# eNode_Spark.net
KiCad netlist of a schematic drawn in EAGLE
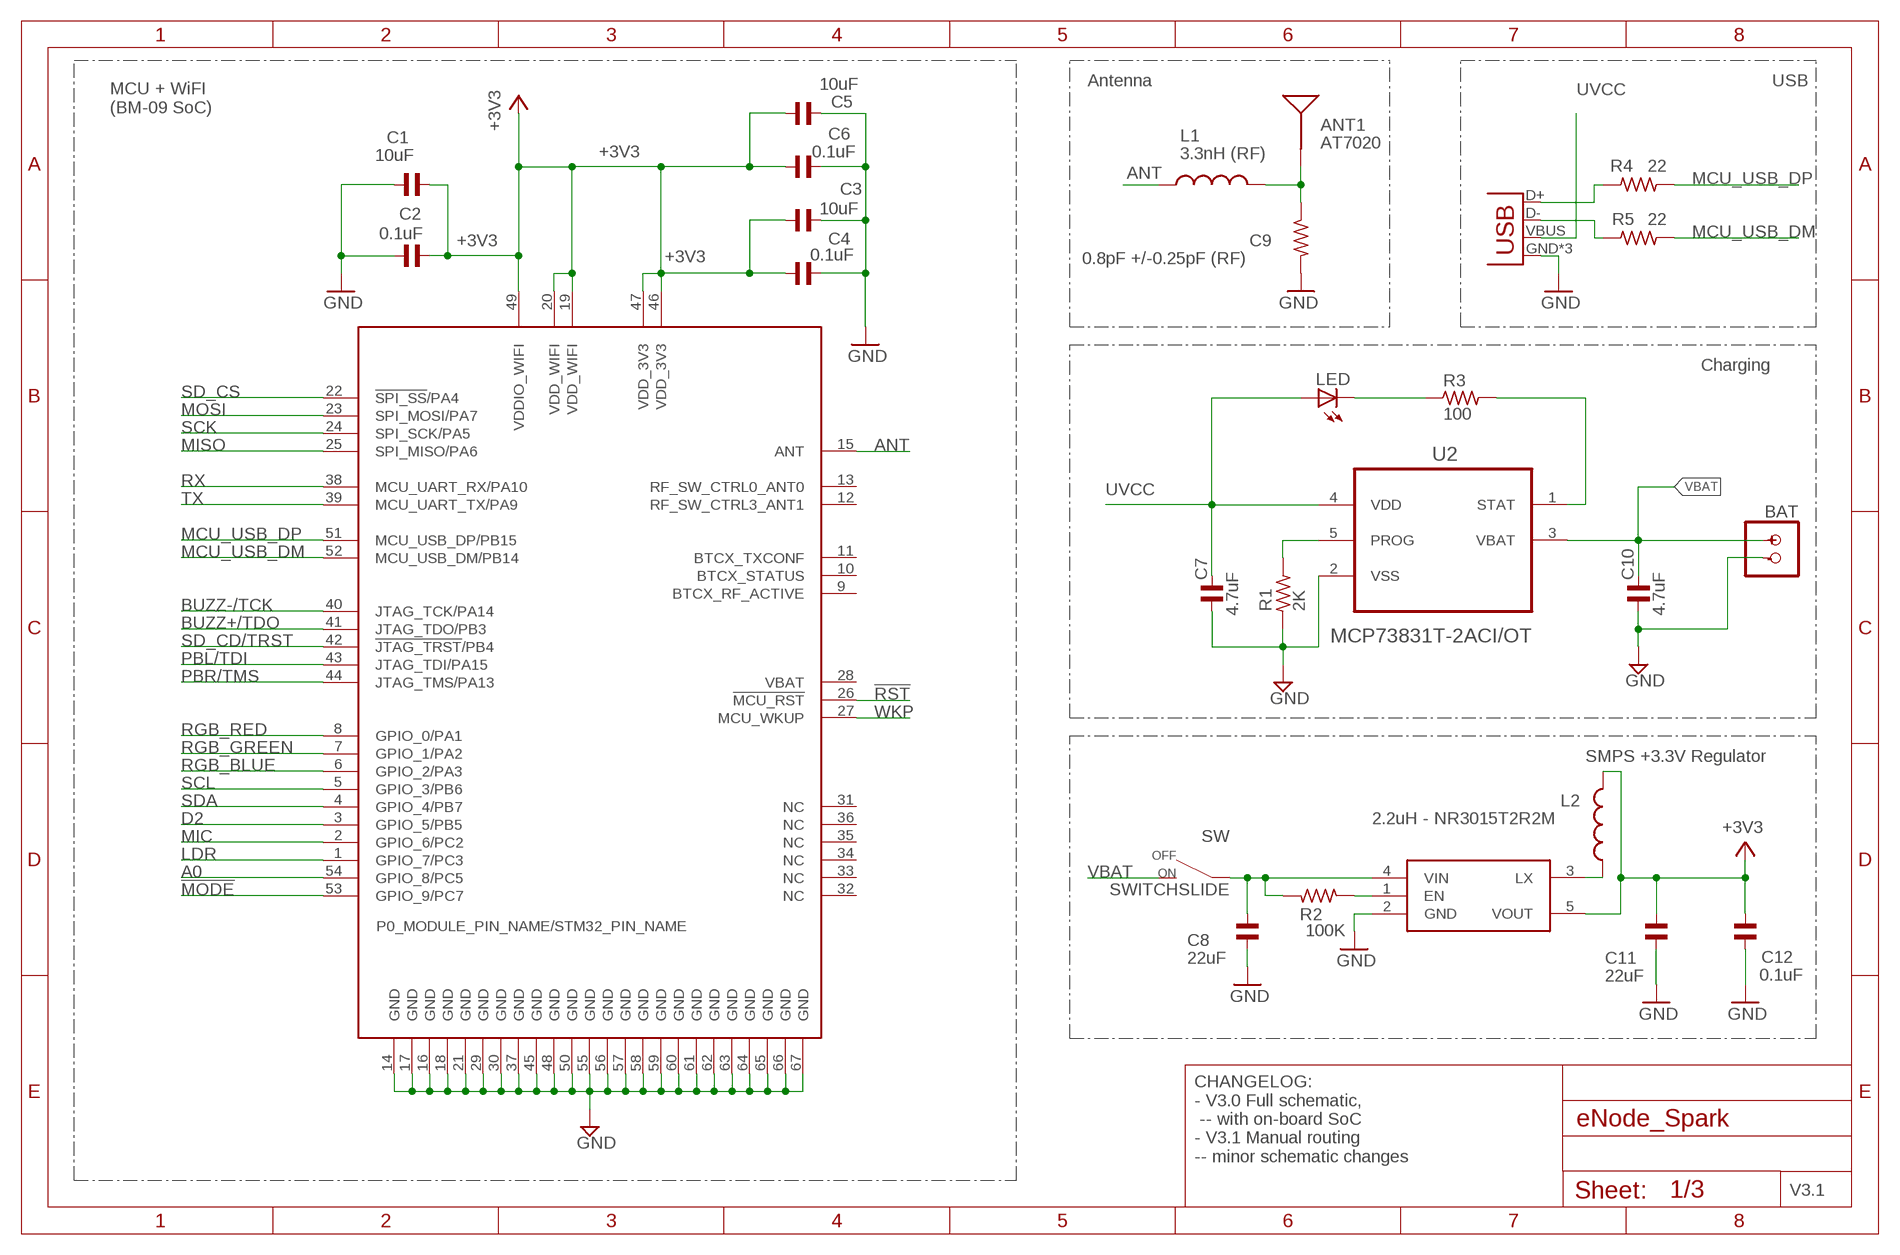
[diagram p0: schematic, sheet 1]
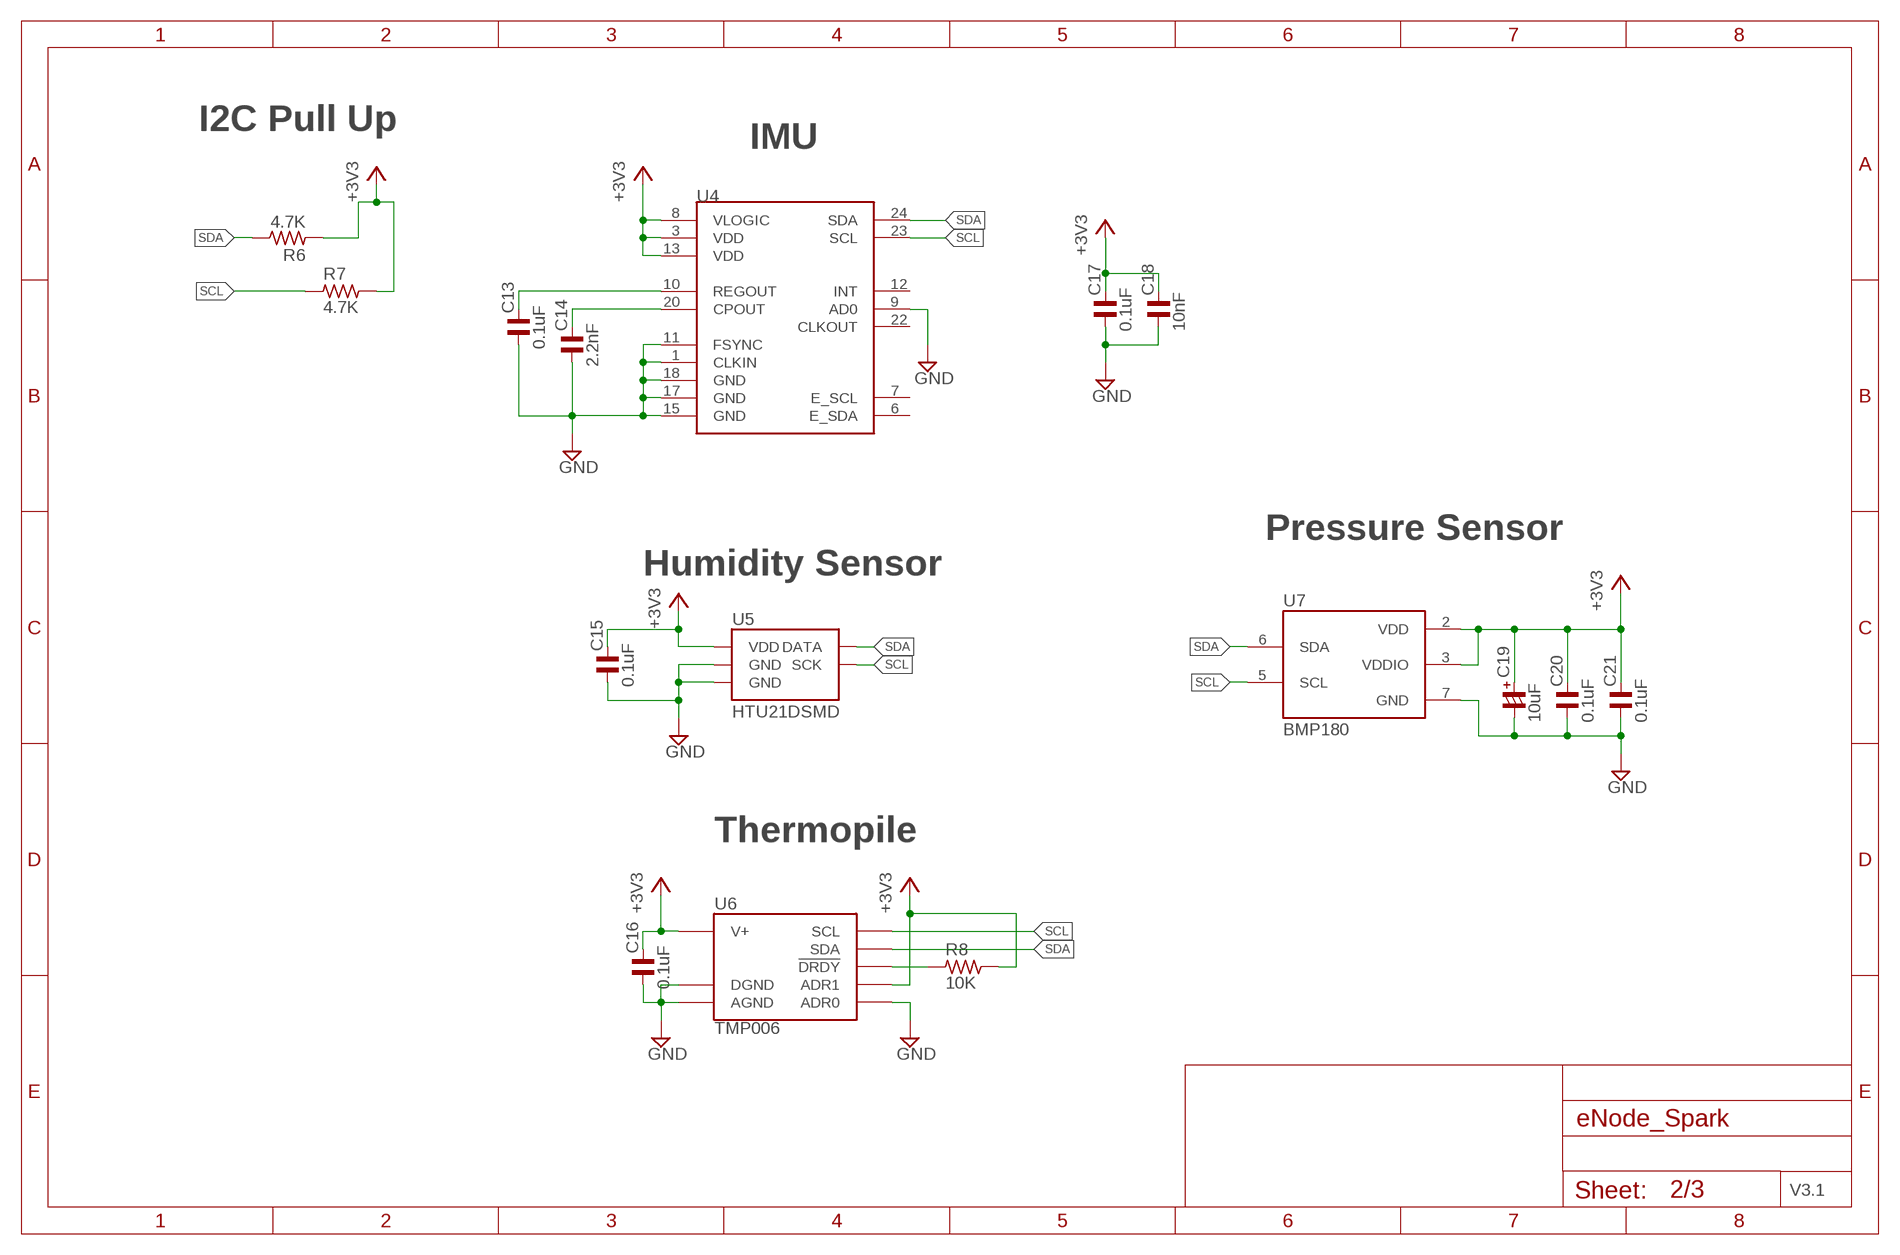
[diagram p1: schematic, sheet 2]
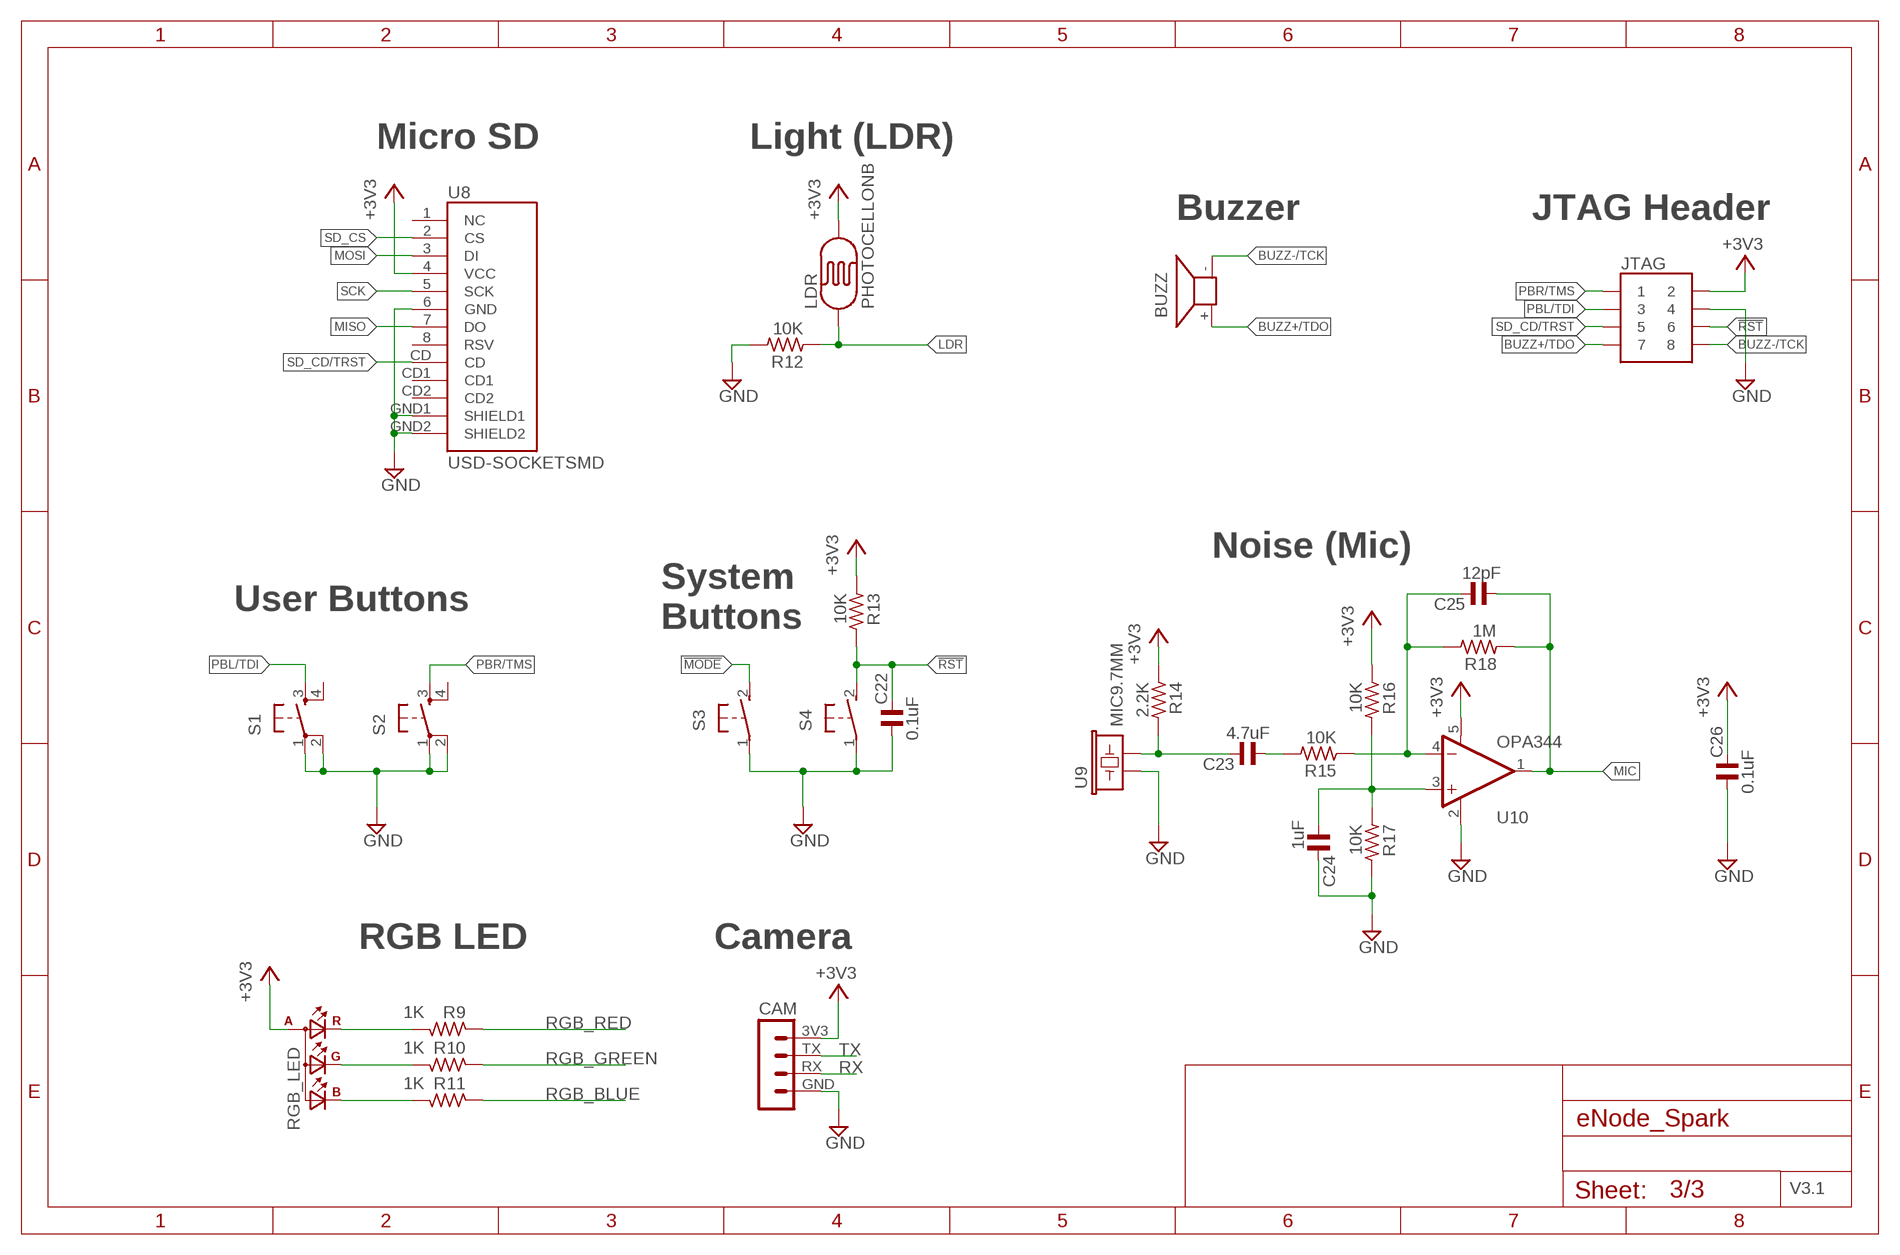
[diagram p2: schematic, sheet 3]

(export (version "E")
  (design (tool "Eeschema 10.0.6"))
  (components
    (comp (ref "ANT1")
      (value "AT7020")
      (footprint "eagle-import:AT7020")
      (libsource (lib "eagle-import") (part "AT7020"))
    )
    (comp (ref "BAT")
      (value "BATTERYSMT")
      (footprint "eagle-import:JST-2-SMD")
      (libsource (lib "eagle-import") (part "BATTERYSMT"))
    )
    (comp (ref "C1")
      (value "10uF")
      (footprint "eagle-import:C0402")
      (libsource (lib "eagle-import") (part "C_0402"))
    )
    (comp (ref "C2")
      (value "0.1uF")
      (footprint "eagle-import:C0402")
      (libsource (lib "eagle-import") (part "C_0402"))
    )
    (comp (ref "C3")
      (value "10uF")
      (footprint "eagle-import:C0402")
      (libsource (lib "eagle-import") (part "C_0402"))
    )
    (comp (ref "C4")
      (value "0.1uF")
      (footprint "eagle-import:C0402")
      (libsource (lib "eagle-import") (part "C_0402"))
    )
    (comp (ref "C5")
      (value "10uF")
      (footprint "eagle-import:C0402")
      (libsource (lib "eagle-import") (part "C_0402"))
    )
    (comp (ref "C6")
      (value "0.1uF")
      (footprint "eagle-import:C0402")
      (libsource (lib "eagle-import") (part "C_0402"))
    )
    (comp (ref "C7")
      (value "4.7uF")
      (footprint "eagle-import:C0402")
      (libsource (lib "eagle-import") (part "C_0402"))
    )
    (comp (ref "C8")
      (value "22uF")
      (footprint "eagle-import:C0603")
      (libsource (lib "eagle-import") (part "C_0603"))
    )
    (comp (ref "C9")
      (value "0.8pF +/-0.25pF (RF)")
      (footprint "eagle-import:R0402_B")
      (libsource (lib "eagle-import") (part "R-US_"))
    )
    (comp (ref "C10")
      (value "4.7uF")
      (footprint "eagle-import:C0402")
      (libsource (lib "eagle-import") (part "C_0402"))
    )
    (comp (ref "C11")
      (value "22uF")
      (footprint "eagle-import:C0603")
      (libsource (lib "eagle-import") (part "C_0603"))
    )
    (comp (ref "C12")
      (value "0.1uF")
      (footprint "eagle-import:C0402")
      (libsource (lib "eagle-import") (part "C_0402"))
    )
    (comp (ref "L1")
      (value "3.3nH (RF)")
      (footprint "eagle-import:L0402_B")
      (libsource (lib "eagle-import") (part "INDUCTOR"))
    )
    (comp (ref "L2")
      (value "2.2uH - NR3015T2R2M")
      (footprint "eagle-import:INDUCTOR-NR3015")
      (libsource (lib "eagle-import") (part "INDUCTORB"))
    )
    (comp (ref "LED")
      (value "LED")
      (footprint "eagle-import:RA_SMD_LED")
      (libsource (lib "eagle-import") (part "LED"))
    )
    (comp (ref "R1")
      (value "2K")
      (footprint "eagle-import:R0603")
      (libsource (lib "eagle-import") (part "R_0603"))
    )
    (comp (ref "R2")
      (value "100K")
      (footprint "eagle-import:R0402")
      (libsource (lib "eagle-import") (part "R_0402"))
    )
    (comp (ref "R3")
      (value "100")
      (footprint "eagle-import:R0603")
      (libsource (lib "eagle-import") (part "R_0603"))
    )
    (comp (ref "R4")
      (value "22")
      (footprint "eagle-import:R0402")
      (libsource (lib "eagle-import") (part "R_0402"))
    )
    (comp (ref "R5")
      (value "22")
      (footprint "eagle-import:R0402")
      (libsource (lib "eagle-import") (part "R_0402"))
    )
    (comp (ref "SW")
      (value "SWITCHSLIDE")
      (footprint "eagle-import:CHANGE_OVER_SLIDE")
      (libsource (lib "eagle-import") (part "SWITCHSLIDE"))
    )
    (comp (ref "U1")
      (value "WM-N-BM-09")
      (footprint "eagle-import:WM-N-BM-09")
      (libsource (lib "eagle-import") (part "WM-N-BM-09"))
    )
    (comp (ref "U2")
      (value "MCP73831T-2ACI/OT")
      (footprint "eagle-import:SOT95P280X145-5N")
      (libsource (lib "eagle-import") (part "MCP73831T-2ACI/OT"))
    )
    (comp (ref "U3")
      (value "R8008-33")
      (footprint "eagle-import:SOT23-5")
      (libsource (lib "eagle-import") (part "R8008-33"))
    )
    (comp (ref "X1")
      (value "USB-MICROB")
      (footprint "eagle-import:USB-MICROB-SLOT-HOLE")
      (libsource (lib "eagle-import") (part "USBUSB-MICROB-SLOT-HOLE"))
    )
    (comp (ref "C13")
      (value "0.1uF")
      (footprint "eagle-import:C0402")
      (libsource (lib "eagle-import") (part "C_0402"))
    )
    (comp (ref "C14")
      (value "2.2nF")
      (footprint "eagle-import:C0402")
      (libsource (lib "eagle-import") (part "C_0402"))
    )
    (comp (ref "C15")
      (value "0.1uF")
      (footprint "eagle-import:C0402")
      (libsource (lib "eagle-import") (part "C_0402"))
    )
    (comp (ref "C16")
      (value "0.1uF")
      (footprint "eagle-import:C0402")
      (libsource (lib "eagle-import") (part "C_0402"))
    )
    (comp (ref "C17")
      (value "0.1uF")
      (footprint "eagle-import:C0402")
      (libsource (lib "eagle-import") (part "C_0402"))
    )
    (comp (ref "C18")
      (value "10nF")
      (footprint "eagle-import:C0402")
      (libsource (lib "eagle-import") (part "C_0402"))
    )
    (comp (ref "C19")
      (value "10uF")
      (footprint "eagle-import:C1206_T")
      (libsource (lib "eagle-import") (part "CP_1206/T"))
    )
    (comp (ref "C20")
      (value "0.1uF")
      (footprint "eagle-import:C0402")
      (libsource (lib "eagle-import") (part "C_0402"))
    )
    (comp (ref "C21")
      (value "0.1uF")
      (footprint "eagle-import:C0402")
      (libsource (lib "eagle-import") (part "C_0402"))
    )
    (comp (ref "R6")
      (value "4.7K")
      (footprint "eagle-import:R0402")
      (libsource (lib "eagle-import") (part "R_0402"))
    )
    (comp (ref "R7")
      (value "4.7K")
      (footprint "eagle-import:R0402")
      (libsource (lib "eagle-import") (part "R_0402"))
    )
    (comp (ref "R8")
      (value "10K")
      (footprint "eagle-import:R0603")
      (libsource (lib "eagle-import") (part "R_0603"))
    )
    (comp (ref "U4")
      (value "MPU-9150QFN-24-NP")
      (footprint "eagle-import:QFN-24-NP")
      (libsource (lib "eagle-import") (part "MPU-9150QFN-24-NP"))
    )
    (comp (ref "U5")
      (value "HTU21DSMD")
      (footprint "eagle-import:HTU21D")
      (libsource (lib "eagle-import") (part "HTU21DSMD"))
    )
    (comp (ref "U6")
      (value "TMP006")
      (footprint "eagle-import:BGA8DS")
      (libsource (lib "eagle-import") (part "TMP006"))
    )
    (comp (ref "U7")
      (value "BMP180")
      (footprint "eagle-import:BMP180")
      (libsource (lib "eagle-import") (part "BMP180"))
    )
    (comp (ref "BUZZ")
      (value "BUZZER")
      (footprint "eagle-import:OFFBOARD_NOSIGN")
      (libsource (lib "eagle-import") (part "BUZZER"))
    )
    (comp (ref "C22")
      (value "0.1uF")
      (footprint "eagle-import:C0402")
      (libsource (lib "eagle-import") (part "C_0402"))
    )
    (comp (ref "C23")
      (value "4.7uF")
      (footprint "eagle-import:C0402")
      (libsource (lib "eagle-import") (part "C_0402"))
    )
    (comp (ref "C24")
      (value "1uF")
      (footprint "eagle-import:C0402")
      (libsource (lib "eagle-import") (part "C_0402"))
    )
    (comp (ref "C25")
      (value "12pF")
      (footprint "eagle-import:C0402")
      (libsource (lib "eagle-import") (part "C_0402"))
    )
    (comp (ref "C26")
      (value "0.1uF")
      (footprint "eagle-import:C0402")
      (libsource (lib "eagle-import") (part "C_0402"))
    )
    (comp (ref "CAM")
      (value "MA04-1")
      (footprint "eagle-import:MA04-1")
      (libsource (lib "eagle-import") (part "MA04-1"))
    )
    (comp (ref "JTAG")
      (value "JTAG_CONNECTOR")
      (footprint "eagle-import:JTAG_DIP")
      (libsource (lib "eagle-import") (part "JTAG_CONNECTOR"))
    )
    (comp (ref "LDR")
      (value "PHOTOCELLONB")
      (footprint "eagle-import:ON_BOARD")
      (libsource (lib "eagle-import") (part "PHOTOCELLONB"))
    )
    (comp (ref "R9")
      (value "1K")
      (footprint "eagle-import:R0402")
      (libsource (lib "eagle-import") (part "R_0402"))
    )
    (comp (ref "R10")
      (value "1K")
      (footprint "eagle-import:R0402")
      (libsource (lib "eagle-import") (part "R_0402"))
    )
    (comp (ref "R11")
      (value "1K")
      (footprint "eagle-import:R0402")
      (libsource (lib "eagle-import") (part "R_0402"))
    )
    (comp (ref "R12")
      (value "10K")
      (footprint "eagle-import:R0603")
      (libsource (lib "eagle-import") (part "R_0603"))
    )
    (comp (ref "R13")
      (value "10K")
      (footprint "eagle-import:R0402")
      (libsource (lib "eagle-import") (part "R_0402"))
    )
    (comp (ref "R14")
      (value "2.2K")
      (footprint "eagle-import:R0402")
      (libsource (lib "eagle-import") (part "R_0402"))
    )
    (comp (ref "R15")
      (value "10K")
      (footprint "eagle-import:R0402")
      (libsource (lib "eagle-import") (part "R_0402"))
    )
    (comp (ref "R16")
      (value "10K")
      (footprint "eagle-import:R0402")
      (libsource (lib "eagle-import") (part "R_0402"))
    )
    (comp (ref "R17")
      (value "10K")
      (footprint "eagle-import:R0402")
      (libsource (lib "eagle-import") (part "R_0402"))
    )
    (comp (ref "R18")
      (value "1M")
      (footprint "eagle-import:R0402")
      (libsource (lib "eagle-import") (part "R_0402"))
    )
    (comp (ref "RGB_LED")
      (value "TOPLED-3PLCC")
      (footprint "eagle-import:P-LCC-4-3")
      (libsource (lib "eagle-import") (part "TOPLED-3PLCC"))
    )
    (comp (ref "S1")
      (value "TAC_SWITCH_4SMD")
      (footprint "eagle-import:TACTILE_SWITCH_SMD_LARGE_4")
      (libsource (lib "eagle-import") (part "TAC_SWITCH_4SMD"))
    )
    (comp (ref "S2")
      (value "TAC_SWITCH_4SMD")
      (footprint "eagle-import:TACTILE_SWITCH_SMD_LARGE_4")
      (libsource (lib "eagle-import") (part "TAC_SWITCH_4SMD"))
    )
    (comp (ref "S3")
      (value "MODE")
      (footprint "eagle-import:DTSM-3")
      (libsource (lib "eagle-import") (part "TAC_SWITCH_2MULTICOMP"))
    )
    (comp (ref "S4")
      (value "RESET")
      (footprint "eagle-import:DTSM-3")
      (libsource (lib "eagle-import") (part "TAC_SWITCH_2MULTICOMP"))
    )
    (comp (ref "U8")
      (value "USD-SOCKETSMD")
      (footprint "eagle-import:MICRO-SD-SOCKET-PP")
      (libsource (lib "eagle-import") (part "USD-SOCKETSMD"))
    )
    (comp (ref "U9")
      (value "MIC9.7MM")
      (footprint "eagle-import:MIC-9.7MM")
      (libsource (lib "eagle-import") (part "MIC9.7MM"))
    )
    (comp (ref "U10")
      (value "OPA344")
      (footprint "eagle-import:SOT23-5")
      (libsource (lib "eagle-import") (part "OPA344"))
    )
  )
  (nets
    (net (code "1") (name "+3V3") (class "Default")
      (node (ref "C1") (pin "2") (pinfunction "2_2") (pintype "passive"))
      (node (ref "C11") (pin "1") (pinfunction "1_1") (pintype "passive"))
      (node (ref "C12") (pin "1") (pinfunction "1_1") (pintype "passive"))
      (node (ref "C15") (pin "2") (pinfunction "2_2") (pintype "passive"))
      (node (ref "C16") (pin "2") (pinfunction "2_2") (pintype "passive"))
      (node (ref "C17") (pin "2") (pinfunction "2_2") (pintype "passive"))
      (node (ref "C18") (pin "2") (pinfunction "2_2") (pintype "passive"))
      (node (ref "C19") (pin "+") (pinfunction "+_+") (pintype "passive"))
      (node (ref "C2") (pin "2") (pinfunction "2_2") (pintype "passive"))
      (node (ref "C20") (pin "2") (pinfunction "2_2") (pintype "passive"))
      (node (ref "C21") (pin "2") (pinfunction "2_2") (pintype "passive"))
      (node (ref "C26") (pin "2") (pinfunction "2_2") (pintype "passive"))
      (node (ref "C3") (pin "1") (pinfunction "1_1") (pintype "passive"))
      (node (ref "C4") (pin "2") (pinfunction "2_2") (pintype "passive"))
      (node (ref "C5") (pin "1") (pinfunction "1_1") (pintype "passive"))
      (node (ref "C6") (pin "2") (pinfunction "2_2") (pintype "passive"))
      (node (ref "CAM") (pin "3V3") (pinfunction "3V3_3V3") (pintype "passive"))
      (node (ref "JTAG") (pin "2") (pinfunction "2_2") (pintype "bidirectional"))
      (node (ref "L2") (pin "2") (pinfunction "2_2") (pintype "passive"))
      (node (ref "LDR") (pin "2") (pinfunction "P$2_2") (pintype "bidirectional"))
      (node (ref "R13") (pin "1") (pinfunction "1_1") (pintype "passive"))
      (node (ref "R14") (pin "1") (pinfunction "1_1") (pintype "passive"))
      (node (ref "R16") (pin "1") (pinfunction "1_1") (pintype "passive"))
      (node (ref "R6") (pin "1") (pinfunction "1_1") (pintype "passive"))
      (node (ref "R7") (pin "2") (pinfunction "2_2") (pintype "passive"))
      (node (ref "R8") (pin "2") (pinfunction "2_2") (pintype "passive"))
      (node (ref "RGB_LED") (pin "A") (pinfunction "A2_A") (pintype "passive"))
      (node (ref "U1") (pin "19") (pinfunction "VDD_WIFI_19") (pintype "bidirectional"))
      (node (ref "U1") (pin "20") (pinfunction "VDD_WIFI_20") (pintype "bidirectional"))
      (node (ref "U1") (pin "46") (pinfunction "VDD_3V3_46") (pintype "bidirectional"))
      (node (ref "U1") (pin "47") (pinfunction "VDD_3V3_47") (pintype "bidirectional"))
      (node (ref "U1") (pin "49") (pinfunction "VDDIO_WIFI_49") (pintype "bidirectional"))
      (node (ref "U10") (pin "5") (pinfunction "V+_5") (pintype "power_in"))
      (node (ref "U3") (pin "5") (pinfunction "VOUT_5") (pintype "bidirectional"))
      (node (ref "U4") (pin "13") (pinfunction "VDD_13") (pintype "bidirectional"))
      (node (ref "U4") (pin "3") (pinfunction "VDD_3") (pintype "bidirectional"))
      (node (ref "U4") (pin "8") (pinfunction "VLOGIC_8") (pintype "bidirectional"))
      (node (ref "U5") (pin "VDD") (pinfunction "VDD_VDD") (pintype "power_in"))
      (node (ref "U6") (pin "A3") (pinfunction "V+_A3") (pintype "bidirectional"))
      (node (ref "U6") (pin "B1") (pinfunction "ADR1_B1") (pintype "bidirectional"))
      (node (ref "U7") (pin "2") (pinfunction "VDD_2") (pintype "power_in"))
      (node (ref "U7") (pin "3") (pinfunction "VDDIO_3") (pintype "power_in"))
      (node (ref "U8") (pin "4") (pinfunction "VCC_4") (pintype "bidirectional"))
    )
    (net (code "2") (name "A0") (class "Default")
      (node (ref "U1") (pin "54") (pinfunction "GPIO_8/PC5_54") (pintype "bidirectional"))
    )
    (net (code "3") (name "ANT") (class "Default")
      (node (ref "L1") (pin "1") (pinfunction "1_1") (pintype "passive"))
      (node (ref "U1") (pin "15") (pinfunction "ANT_15") (pintype "bidirectional"))
    )
    (net (code "4") (name "BUZZ+{slash}TDO") (class "Default")
      (node (ref "BUZZ") (pin "+") (pinfunction "+_+") (pintype "passive"))
      (node (ref "JTAG") (pin "7") (pinfunction "7_7") (pintype "bidirectional"))
      (node (ref "U1") (pin "41") (pinfunction "JTAG_TDO/PB3_41") (pintype "bidirectional"))
    )
    (net (code "5") (name "BUZZ-{slash}TCK") (class "Default")
      (node (ref "BUZZ") (pin "-") (pinfunction "-_-") (pintype "passive"))
      (node (ref "JTAG") (pin "8") (pinfunction "8_8") (pintype "bidirectional"))
      (node (ref "U1") (pin "40") (pinfunction "JTAG_TCK/PA14_40") (pintype "bidirectional"))
    )
    (net (code "6") (name "D2") (class "Default")
      (node (ref "U1") (pin "3") (pinfunction "GPIO_5/PB5_3") (pintype "bidirectional"))
    )
    (net (code "7") (name "GND") (class "Default")
      (node (ref "BAT") (pin "-") (pinfunction "-_-") (pintype "passive"))
      (node (ref "C1") (pin "1") (pinfunction "1_1") (pintype "passive"))
      (node (ref "C10") (pin "1") (pinfunction "1_1") (pintype "passive"))
      (node (ref "C11") (pin "2") (pinfunction "2_2") (pintype "passive"))
      (node (ref "C12") (pin "2") (pinfunction "2_2") (pintype "passive"))
      (node (ref "C13") (pin "1") (pinfunction "1_1") (pintype "passive"))
      (node (ref "C14") (pin "1") (pinfunction "1_1") (pintype "passive"))
      (node (ref "C15") (pin "1") (pinfunction "1_1") (pintype "passive"))
      (node (ref "C16") (pin "1") (pinfunction "1_1") (pintype "passive"))
      (node (ref "C17") (pin "1") (pinfunction "1_1") (pintype "passive"))
      (node (ref "C18") (pin "1") (pinfunction "1_1") (pintype "passive"))
      (node (ref "C19") (pin "-") (pinfunction "-_-") (pintype "passive"))
      (node (ref "C2") (pin "1") (pinfunction "1_1") (pintype "passive"))
      (node (ref "C20") (pin "1") (pinfunction "1_1") (pintype "passive"))
      (node (ref "C21") (pin "1") (pinfunction "1_1") (pintype "passive"))
      (node (ref "C22") (pin "1") (pinfunction "1_1") (pintype "passive"))
      (node (ref "C24") (pin "2") (pinfunction "2_2") (pintype "passive"))
      (node (ref "C26") (pin "1") (pinfunction "1_1") (pintype "passive"))
      (node (ref "C3") (pin "2") (pinfunction "2_2") (pintype "passive"))
      (node (ref "C4") (pin "1") (pinfunction "1_1") (pintype "passive"))
      (node (ref "C5") (pin "2") (pinfunction "2_2") (pintype "passive"))
      (node (ref "C6") (pin "1") (pinfunction "1_1") (pintype "passive"))
      (node (ref "C7") (pin "1") (pinfunction "1_1") (pintype "passive"))
      (node (ref "C8") (pin "2") (pinfunction "2_2") (pintype "passive"))
      (node (ref "C9") (pin "2") (pinfunction "2_2") (pintype "passive"))
      (node (ref "CAM") (pin "GND") (pinfunction "GND_GND") (pintype "passive"))
      (node (ref "JTAG") (pin "4") (pinfunction "4_4") (pintype "bidirectional"))
      (node (ref "R1") (pin "1") (pinfunction "1_1") (pintype "passive"))
      (node (ref "R12") (pin "2") (pinfunction "2_2") (pintype "passive"))
      (node (ref "R17") (pin "2") (pinfunction "2_2") (pintype "passive"))
      (node (ref "S1") (pin "1") (pinfunction "1_1") (pintype "passive"))
      (node (ref "S1") (pin "2") (pinfunction "2_2") (pintype "passive"))
      (node (ref "S2") (pin "1") (pinfunction "1_1") (pintype "passive"))
      (node (ref "S2") (pin "2") (pinfunction "2_2") (pintype "passive"))
      (node (ref "S3") (pin "1") (pinfunction "1_1") (pintype "passive"))
      (node (ref "S4") (pin "1") (pinfunction "1_1") (pintype "passive"))
      (node (ref "U1") (pin "14") (pinfunction "GND_14") (pintype "bidirectional"))
      (node (ref "U1") (pin "16") (pinfunction "GND_16") (pintype "bidirectional"))
      (node (ref "U1") (pin "17") (pinfunction "GND_17") (pintype "bidirectional"))
      (node (ref "U1") (pin "18") (pinfunction "GND_18") (pintype "bidirectional"))
      (node (ref "U1") (pin "21") (pinfunction "GND_21") (pintype "bidirectional"))
      (node (ref "U1") (pin "29") (pinfunction "GND_29") (pintype "bidirectional"))
      (node (ref "U1") (pin "30") (pinfunction "GND_30") (pintype "bidirectional"))
      (node (ref "U1") (pin "37") (pinfunction "GND_37") (pintype "bidirectional"))
      (node (ref "U1") (pin "45") (pinfunction "GND_45") (pintype "bidirectional"))
      (node (ref "U1") (pin "48") (pinfunction "GND_48") (pintype "bidirectional"))
      (node (ref "U1") (pin "50") (pinfunction "GND_50") (pintype "bidirectional"))
      (node (ref "U1") (pin "55") (pinfunction "GND_55") (pintype "bidirectional"))
      (node (ref "U1") (pin "56") (pinfunction "GND_56") (pintype "bidirectional"))
      (node (ref "U1") (pin "57") (pinfunction "GND_57") (pintype "bidirectional"))
      (node (ref "U1") (pin "58") (pinfunction "GND_58") (pintype "bidirectional"))
      (node (ref "U1") (pin "59") (pinfunction "GND_59") (pintype "bidirectional"))
      (node (ref "U1") (pin "60") (pinfunction "GND_60") (pintype "bidirectional"))
      (node (ref "U1") (pin "61") (pinfunction "GND_61") (pintype "bidirectional"))
      (node (ref "U1") (pin "62") (pinfunction "GND_62") (pintype "bidirectional"))
      (node (ref "U1") (pin "63") (pinfunction "GND_63") (pintype "bidirectional"))
      (node (ref "U1") (pin "64") (pinfunction "GND_64") (pintype "bidirectional"))
      (node (ref "U1") (pin "65") (pinfunction "GND_65") (pintype "bidirectional"))
      (node (ref "U1") (pin "66") (pinfunction "GND_66") (pintype "bidirectional"))
      (node (ref "U1") (pin "67") (pinfunction "GND_67") (pintype "bidirectional"))
      (node (ref "U10") (pin "2") (pinfunction "V-_2") (pintype "power_in"))
      (node (ref "U2") (pin "2") (pinfunction "VSS_2") (pintype "power_in"))
      (node (ref "U3") (pin "2") (pinfunction "GND_2") (pintype "bidirectional"))
      (node (ref "U4") (pin "1") (pinfunction "CLKIN_1") (pintype "bidirectional"))
      (node (ref "U4") (pin "11") (pinfunction "FSYNC_11") (pintype "bidirectional"))
      (node (ref "U4") (pin "15") (pinfunction "GND_15") (pintype "bidirectional"))
      (node (ref "U4") (pin "17") (pinfunction "GND_17") (pintype "bidirectional"))
      (node (ref "U4") (pin "18") (pinfunction "GND_18") (pintype "bidirectional"))
      (node (ref "U4") (pin "9") (pinfunction "AD0_9") (pintype "bidirectional"))
      (node (ref "U5") (pin "7") (pinfunction "GND_7") (pintype "power_in"))
      (node (ref "U5") (pin "GND") (pinfunction "GND_GND") (pintype "power_in"))
      (node (ref "U6") (pin "A1") (pinfunction "DGND_A1") (pintype "bidirectional"))
      (node (ref "U6") (pin "A2") (pinfunction "AGND_A2") (pintype "bidirectional"))
      (node (ref "U6") (pin "C1") (pinfunction "ADR0_C1") (pintype "bidirectional"))
      (node (ref "U7") (pin "7") (pinfunction "GND_7") (pintype "power_in"))
      (node (ref "U8") (pin "6") (pinfunction "GND_6") (pintype "bidirectional"))
      (node (ref "U8") (pin "GND1") (pinfunction "SHIELD1_GND1") (pintype "bidirectional"))
      (node (ref "U8") (pin "GND2") (pinfunction "SHIELD2_GND2") (pintype "bidirectional"))
      (node (ref "U9") (pin "1") (pinfunction "1_1") (pintype "passive"))
      (node (ref "X1") (pin "GND") (pinfunction "GND_GND") (pintype "bidirectional"))
      (node (ref "X1") (pin "MT1") (pinfunction "GND_MT1") (pintype "bidirectional"))
      (node (ref "X1") (pin "MT2") (pinfunction "GND_MT2") (pintype "bidirectional"))
    )
    (net (code "8") (name "LDR") (class "Default")
      (node (ref "LDR") (pin "1") (pinfunction "P$1_1") (pintype "bidirectional"))
      (node (ref "R12") (pin "1") (pinfunction "1_1") (pintype "passive"))
      (node (ref "U1") (pin "1") (pinfunction "GPIO_7/PC3_1") (pintype "bidirectional"))
    )
    (net (code "9") (name "MCU_USB_DM") (class "Default")
      (node (ref "R5") (pin "1") (pinfunction "1_1") (pintype "passive"))
      (node (ref "U1") (pin "52") (pinfunction "MCU_USB_DM/PB14_52") (pintype "bidirectional"))
    )
    (net (code "10") (name "MCU_USB_DP") (class "Default")
      (node (ref "R4") (pin "1") (pinfunction "1_1") (pintype "passive"))
      (node (ref "U1") (pin "51") (pinfunction "MCU_USB_DP/PB15_51") (pintype "bidirectional"))
    )
    (net (code "11") (name "MIC") (class "Default")
      (node (ref "C25") (pin "1") (pinfunction "1_1") (pintype "passive"))
      (node (ref "R18") (pin "1") (pinfunction "1_1") (pintype "passive"))
      (node (ref "U1") (pin "2") (pinfunction "GPIO_6/PC2_2") (pintype "bidirectional"))
      (node (ref "U10") (pin "1") (pinfunction "OUT_1") (pintype "output"))
    )
    (net (code "12") (name "MISO") (class "Default")
      (node (ref "U1") (pin "25") (pinfunction "SPI_MISO/PA6_25") (pintype "bidirectional"))
      (node (ref "U8") (pin "7") (pinfunction "DO_7") (pintype "bidirectional"))
    )
    (net (code "13") (name "MOSI") (class "Default")
      (node (ref "U1") (pin "23") (pinfunction "SPI_MOSI/PA7_23") (pintype "bidirectional"))
      (node (ref "U8") (pin "3") (pinfunction "DI_3") (pintype "bidirectional"))
    )
    (net (code "14") (name "Net-(ANT1-SIGNAL)") (class "Default")
      (node (ref "ANT1") (pin "1") (pinfunction "SIGNAL_1") (pintype "bidirectional"))
      (node (ref "C9") (pin "1") (pinfunction "1_1") (pintype "passive"))
      (node (ref "L1") (pin "2") (pinfunction "2_2") (pintype "passive"))
    )
    (net (code "15") (name "Net-(C23-Pad1)") (class "Default")
      (node (ref "C23") (pin "1") (pinfunction "1_1") (pintype "passive"))
      (node (ref "R15") (pin "2") (pinfunction "2_2") (pintype "passive"))
    )
    (net (code "16") (name "Net-(C23-Pad2)") (class "Default")
      (node (ref "C23") (pin "2") (pinfunction "2_2") (pintype "passive"))
      (node (ref "R14") (pin "2") (pinfunction "2_2") (pintype "passive"))
      (node (ref "U9") (pin "2") (pinfunction "2_2") (pintype "passive"))
    )
    (net (code "17") (name "Net-(LED-PadC)") (class "Default")
      (node (ref "LED") (pin "C") (pinfunction "C_C") (pintype "passive"))
      (node (ref "R3") (pin "1") (pinfunction "1_1") (pintype "passive"))
    )
    (net (code "18") (name "Net-(R4-Pad2)") (class "Default")
      (node (ref "R4") (pin "2") (pinfunction "2_2") (pintype "passive"))
      (node (ref "X1") (pin "D+") (pinfunction "D+_D+") (pintype "bidirectional"))
    )
    (net (code "19") (name "Net-(R5-Pad2)") (class "Default")
      (node (ref "R5") (pin "2") (pinfunction "2_2") (pintype "passive"))
      (node (ref "X1") (pin "D-") (pinfunction "D-_D-") (pintype "bidirectional"))
    )
    (net (code "20") (name "Net-(RGB_LED-CBLUE)") (class "Default")
      (node (ref "R11") (pin "1") (pinfunction "1_1") (pintype "passive"))
      (node (ref "RGB_LED") (pin "B") (pinfunction "CBLUE_B") (pintype "passive"))
    )
    (net (code "21") (name "Net-(RGB_LED-CGREEN)") (class "Default")
      (node (ref "R10") (pin "1") (pinfunction "1_1") (pintype "passive"))
      (node (ref "RGB_LED") (pin "G") (pinfunction "CGREEN_G") (pintype "passive"))
    )
    (net (code "22") (name "Net-(RGB_LED-CRED)") (class "Default")
      (node (ref "R9") (pin "1") (pinfunction "1_1") (pintype "passive"))
      (node (ref "RGB_LED") (pin "R") (pinfunction "CRED_R") (pintype "passive"))
    )
    (net (code "23") (name "Net-(U2-PROG)") (class "Default")
      (node (ref "R1") (pin "2") (pinfunction "2_2") (pintype "passive"))
      (node (ref "U2") (pin "5") (pinfunction "PROG_5") (pintype "input"))
    )
    (net (code "24") (name "Net-(U2-STAT)") (class "Default")
      (node (ref "R3") (pin "2") (pinfunction "2_2") (pintype "passive"))
      (node (ref "U2") (pin "1") (pinfunction "STAT_1") (pintype "output"))
    )
    (net (code "25") (name "Net-(U3-EN)") (class "Default")
      (node (ref "R2") (pin "1") (pinfunction "1_1") (pintype "passive"))
      (node (ref "U3") (pin "1") (pinfunction "EN_1") (pintype "bidirectional"))
    )
    (net (code "26") (name "Net-(U3-LX)") (class "Default")
      (node (ref "L2") (pin "1") (pinfunction "1_1") (pintype "passive"))
      (node (ref "U3") (pin "3") (pinfunction "LX_3") (pintype "bidirectional"))
    )
    (net (code "27") (name "Net-(U3-VIN)") (class "Default")
      (node (ref "C8") (pin "1") (pinfunction "1_1") (pintype "passive"))
      (node (ref "R2") (pin "2") (pinfunction "2_2") (pintype "passive"))
      (node (ref "SW") (pin "1") (pinfunction "1_1") (pintype "bidirectional"))
      (node (ref "U3") (pin "4") (pinfunction "VIN_4") (pintype "bidirectional"))
    )
    (net (code "28") (name "Net-(U4-CPOUT)") (class "Default")
      (node (ref "C14") (pin "2") (pinfunction "2_2") (pintype "passive"))
      (node (ref "U4") (pin "20") (pinfunction "CPOUT_20") (pintype "bidirectional"))
    )
    (net (code "29") (name "Net-(U4-REGOUT)") (class "Default")
      (node (ref "C13") (pin "2") (pinfunction "2_2") (pintype "passive"))
      (node (ref "U4") (pin "10") (pinfunction "REGOUT_10") (pintype "bidirectional"))
    )
    (net (code "30") (name "Net-(U6-~{DRDY})") (class "Default")
      (node (ref "R8") (pin "1") (pinfunction "1_1") (pintype "passive"))
      (node (ref "U6") (pin "C2") (pinfunction "~{DRDY}_C2") (pintype "bidirectional"))
    )
    (net (code "31") (name "Net-(U10-+IN)") (class "Default")
      (node (ref "C24") (pin "1") (pinfunction "1_1") (pintype "passive"))
      (node (ref "R16") (pin "2") (pinfunction "2_2") (pintype "passive"))
      (node (ref "R17") (pin "1") (pinfunction "1_1") (pintype "passive"))
      (node (ref "U10") (pin "3") (pinfunction "+IN_3") (pintype "input"))
    )
    (net (code "32") (name "Net-(U10--IN)") (class "Default")
      (node (ref "C25") (pin "2") (pinfunction "2_2") (pintype "passive"))
      (node (ref "R15") (pin "1") (pinfunction "1_1") (pintype "passive"))
      (node (ref "R18") (pin "2") (pinfunction "2_2") (pintype "passive"))
      (node (ref "U10") (pin "4") (pinfunction "-IN_4") (pintype "input"))
    )
    (net (code "33") (name "PBL{slash}TDI") (class "Default")
      (node (ref "JTAG") (pin "3") (pinfunction "3_3") (pintype "bidirectional"))
      (node (ref "S1") (pin "3") (pinfunction "3_3") (pintype "passive"))
      (node (ref "U1") (pin "43") (pinfunction "JTAG_TDI/PA15_43") (pintype "bidirectional"))
    )
    (net (code "34") (name "PBR{slash}TMS") (class "Default")
      (node (ref "JTAG") (pin "1") (pinfunction "1_1") (pintype "bidirectional"))
      (node (ref "S2") (pin "3") (pinfunction "3_3") (pintype "passive"))
      (node (ref "U1") (pin "44") (pinfunction "JTAG_TMS/PA13_44") (pintype "bidirectional"))
    )
    (net (code "35") (name "RGB_BLUE") (class "Default")
      (node (ref "R11") (pin "2") (pinfunction "2_2") (pintype "passive"))
      (node (ref "U1") (pin "6") (pinfunction "GPIO_2/PA3_6") (pintype "bidirectional"))
    )
    (net (code "36") (name "RGB_GREEN") (class "Default")
      (node (ref "R10") (pin "2") (pinfunction "2_2") (pintype "passive"))
      (node (ref "U1") (pin "7") (pinfunction "GPIO_1/PA2_7") (pintype "bidirectional"))
    )
    (net (code "37") (name "RGB_RED") (class "Default")
      (node (ref "R9") (pin "2") (pinfunction "2_2") (pintype "passive"))
      (node (ref "U1") (pin "8") (pinfunction "GPIO_0/PA1_8") (pintype "bidirectional"))
    )
    (net (code "38") (name "RX") (class "Default")
      (node (ref "CAM") (pin "RX") (pinfunction "RX_RX") (pintype "passive"))
      (node (ref "U1") (pin "38") (pinfunction "MCU_UART_RX/PA10_38") (pintype "bidirectional"))
    )
    (net (code "39") (name "SCK") (class "Default")
      (node (ref "U1") (pin "24") (pinfunction "SPI_SCK/PA5_24") (pintype "bidirectional"))
      (node (ref "U8") (pin "5") (pinfunction "SCK_5") (pintype "bidirectional"))
    )
    (net (code "40") (name "SCL") (class "Default")
      (node (ref "R7") (pin "1") (pinfunction "1_1") (pintype "passive"))
      (node (ref "U1") (pin "5") (pinfunction "GPIO_3/PB6_5") (pintype "bidirectional"))
      (node (ref "U4") (pin "23") (pinfunction "SCL_23") (pintype "bidirectional"))
      (node (ref "U5") (pin "SCK") (pinfunction "SCK_SCK") (pintype "input"))
      (node (ref "U6") (pin "B3") (pinfunction "SCL_B3") (pintype "bidirectional"))
      (node (ref "U7") (pin "5") (pinfunction "SCL_5") (pintype "input"))
    )
    (net (code "41") (name "SDA") (class "Default")
      (node (ref "R6") (pin "2") (pinfunction "2_2") (pintype "passive"))
      (node (ref "U1") (pin "4") (pinfunction "GPIO_4/PB7_4") (pintype "bidirectional"))
      (node (ref "U4") (pin "24") (pinfunction "SDA_24") (pintype "bidirectional"))
      (node (ref "U5") (pin "DATA") (pinfunction "DATA_DATA") (pintype "bidirectional"))
      (node (ref "U6") (pin "C3") (pinfunction "SDA_C3") (pintype "bidirectional"))
      (node (ref "U7") (pin "6") (pinfunction "SDA_6") (pintype "bidirectional"))
    )
    (net (code "42") (name "SD_CD{slash}TRST") (class "Default")
      (node (ref "JTAG") (pin "5") (pinfunction "5_5") (pintype "bidirectional"))
      (node (ref "U1") (pin "42") (pinfunction "~{JTAG_TRST}/PB4_42") (pintype "bidirectional"))
      (node (ref "U8") (pin "CD") (pinfunction "CD_CD") (pintype "bidirectional"))
    )
    (net (code "43") (name "SD_CS") (class "Default")
      (node (ref "U1") (pin "22") (pinfunction "~{SPI_SS}/PA4_22") (pintype "bidirectional"))
      (node (ref "U8") (pin "2") (pinfunction "CS_2") (pintype "bidirectional"))
    )
    (net (code "44") (name "TX") (class "Default")
      (node (ref "CAM") (pin "TX") (pinfunction "TX_TX") (pintype "passive"))
      (node (ref "U1") (pin "39") (pinfunction "MCU_UART_TX/PA9_39") (pintype "bidirectional"))
    )
    (net (code "45") (name "UVCC") (class "Default")
      (node (ref "C7") (pin "2") (pinfunction "2_2") (pintype "passive"))
      (node (ref "LED") (pin "A") (pinfunction "A_A") (pintype "passive"))
      (node (ref "U2") (pin "4") (pinfunction "VDD_4") (pintype "power_in"))
      (node (ref "X1") (pin "VBUS") (pinfunction "VBUS_VBUS") (pintype "bidirectional"))
    )
    (net (code "46") (name "VBAT") (class "Default")
      (node (ref "BAT") (pin "+") (pinfunction "+_+") (pintype "passive"))
      (node (ref "C10") (pin "2") (pinfunction "2_2") (pintype "passive"))
      (node (ref "SW") (pin "2") (pinfunction "2_2") (pintype "bidirectional"))
      (node (ref "U2") (pin "3") (pinfunction "VBAT_3") (pintype "output"))
    )
    (net (code "47") (name "WKP") (class "Default")
      (node (ref "U1") (pin "27") (pinfunction "MCU_WKUP_27") (pintype "bidirectional"))
    )
    (net (code "48") (name "unconnected-(S1-Pad4)") (class "Default")
      (node (ref "S1") (pin "4") (pinfunction "4_4") (pintype "passive"))
    )
    (net (code "49") (name "unconnected-(S2-Pad4)") (class "Default")
      (node (ref "S2") (pin "4") (pinfunction "4_4") (pintype "passive"))
    )
    (net (code "50") (name "unconnected-(U1-BTCX_RF_ACTIVE-Pad9)") (class "Default")
      (node (ref "U1") (pin "9") (pinfunction "BTCX_RF_ACTIVE_9") (pintype "bidirectional"))
    )
    (net (code "51") (name "unconnected-(U1-BTCX_STATUS-Pad10)") (class "Default")
      (node (ref "U1") (pin "10") (pinfunction "BTCX_STATUS_10") (pintype "bidirectional"))
    )
    (net (code "52") (name "unconnected-(U1-BTCX_TXCONF-Pad11)") (class "Default")
      (node (ref "U1") (pin "11") (pinfunction "BTCX_TXCONF_11") (pintype "bidirectional"))
    )
    (net (code "53") (name "unconnected-(U1-NC-Pad31)") (class "Default")
      (node (ref "U1") (pin "31") (pinfunction "NC_31") (pintype "bidirectional"))
    )
    (net (code "54") (name "unconnected-(U1-NC-Pad32)") (class "Default")
      (node (ref "U1") (pin "32") (pinfunction "NC_32") (pintype "bidirectional"))
    )
    (net (code "55") (name "unconnected-(U1-NC-Pad33)") (class "Default")
      (node (ref "U1") (pin "33") (pinfunction "NC_33") (pintype "bidirectional"))
    )
    (net (code "56") (name "unconnected-(U1-NC-Pad34)") (class "Default")
      (node (ref "U1") (pin "34") (pinfunction "NC_34") (pintype "bidirectional"))
    )
    (net (code "57") (name "unconnected-(U1-NC-Pad35)") (class "Default")
      (node (ref "U1") (pin "35") (pinfunction "NC_35") (pintype "bidirectional"))
    )
    (net (code "58") (name "unconnected-(U1-NC-Pad36)") (class "Default")
      (node (ref "U1") (pin "36") (pinfunction "NC_36") (pintype "bidirectional"))
    )
    (net (code "59") (name "unconnected-(U1-RF_SW_CTRL0_ANT0-Pad13)") (class "Default")
      (node (ref "U1") (pin "13") (pinfunction "RF_SW_CTRL0_ANT0_13") (pintype "bidirectional"))
    )
    (net (code "60") (name "unconnected-(U1-RF_SW_CTRL3_ANT1-Pad12)") (class "Default")
      (node (ref "U1") (pin "12") (pinfunction "RF_SW_CTRL3_ANT1_12") (pintype "bidirectional"))
    )
    (net (code "61") (name "unconnected-(U1-VBAT-Pad28)") (class "Default")
      (node (ref "U1") (pin "28") (pinfunction "VBAT_28") (pintype "bidirectional"))
    )
    (net (code "62") (name "unconnected-(U4-CLKOUT-Pad22)") (class "Default")
      (node (ref "U4") (pin "22") (pinfunction "CLKOUT_22") (pintype "bidirectional"))
    )
    (net (code "63") (name "unconnected-(U4-E_SCL-Pad7)") (class "Default")
      (node (ref "U4") (pin "7") (pinfunction "E_SCL_7") (pintype "bidirectional"))
    )
    (net (code "64") (name "unconnected-(U4-E_SDA-Pad6)") (class "Default")
      (node (ref "U4") (pin "6") (pinfunction "E_SDA_6") (pintype "bidirectional"))
    )
    (net (code "65") (name "unconnected-(U4-INT-Pad12)") (class "Default")
      (node (ref "U4") (pin "12") (pinfunction "INT_12") (pintype "bidirectional"))
    )
    (net (code "66") (name "unconnected-(U8-NC-Pad1)") (class "Default")
      (node (ref "U8") (pin "1") (pinfunction "NC_1") (pintype "bidirectional"))
    )
    (net (code "67") (name "unconnected-(U8-PadCD1)") (class "Default")
      (node (ref "U8") (pin "CD1") (pinfunction "CD1_CD1") (pintype "bidirectional"))
    )
    (net (code "68") (name "unconnected-(U8-PadCD2)") (class "Default")
      (node (ref "U8") (pin "CD2") (pinfunction "CD2_CD2") (pintype "bidirectional"))
    )
    (net (code "69") (name "unconnected-(U8-RSV-Pad8)") (class "Default")
      (node (ref "U8") (pin "8") (pinfunction "RSV_8") (pintype "bidirectional"))
    )
    (net (code "70") (name "~{MODE}") (class "Default")
      (node (ref "S3") (pin "2") (pinfunction "2_2") (pintype "passive"))
      (node (ref "U1") (pin "53") (pinfunction "GPIO_9/PC7_53") (pintype "bidirectional"))
    )
    (net (code "71") (name "~{RST}") (class "Default")
      (node (ref "C22") (pin "2") (pinfunction "2_2") (pintype "passive"))
      (node (ref "JTAG") (pin "6") (pinfunction "6_6") (pintype "bidirectional"))
      (node (ref "R13") (pin "2") (pinfunction "2_2") (pintype "passive"))
      (node (ref "S4") (pin "2") (pinfunction "2_2") (pintype "passive"))
      (node (ref "U1") (pin "26") (pinfunction "~{MCU_RST}_26") (pintype "bidirectional"))
    )
  )
)
